# module.net
KiCad netlist of a schematic drawn in EAGLE
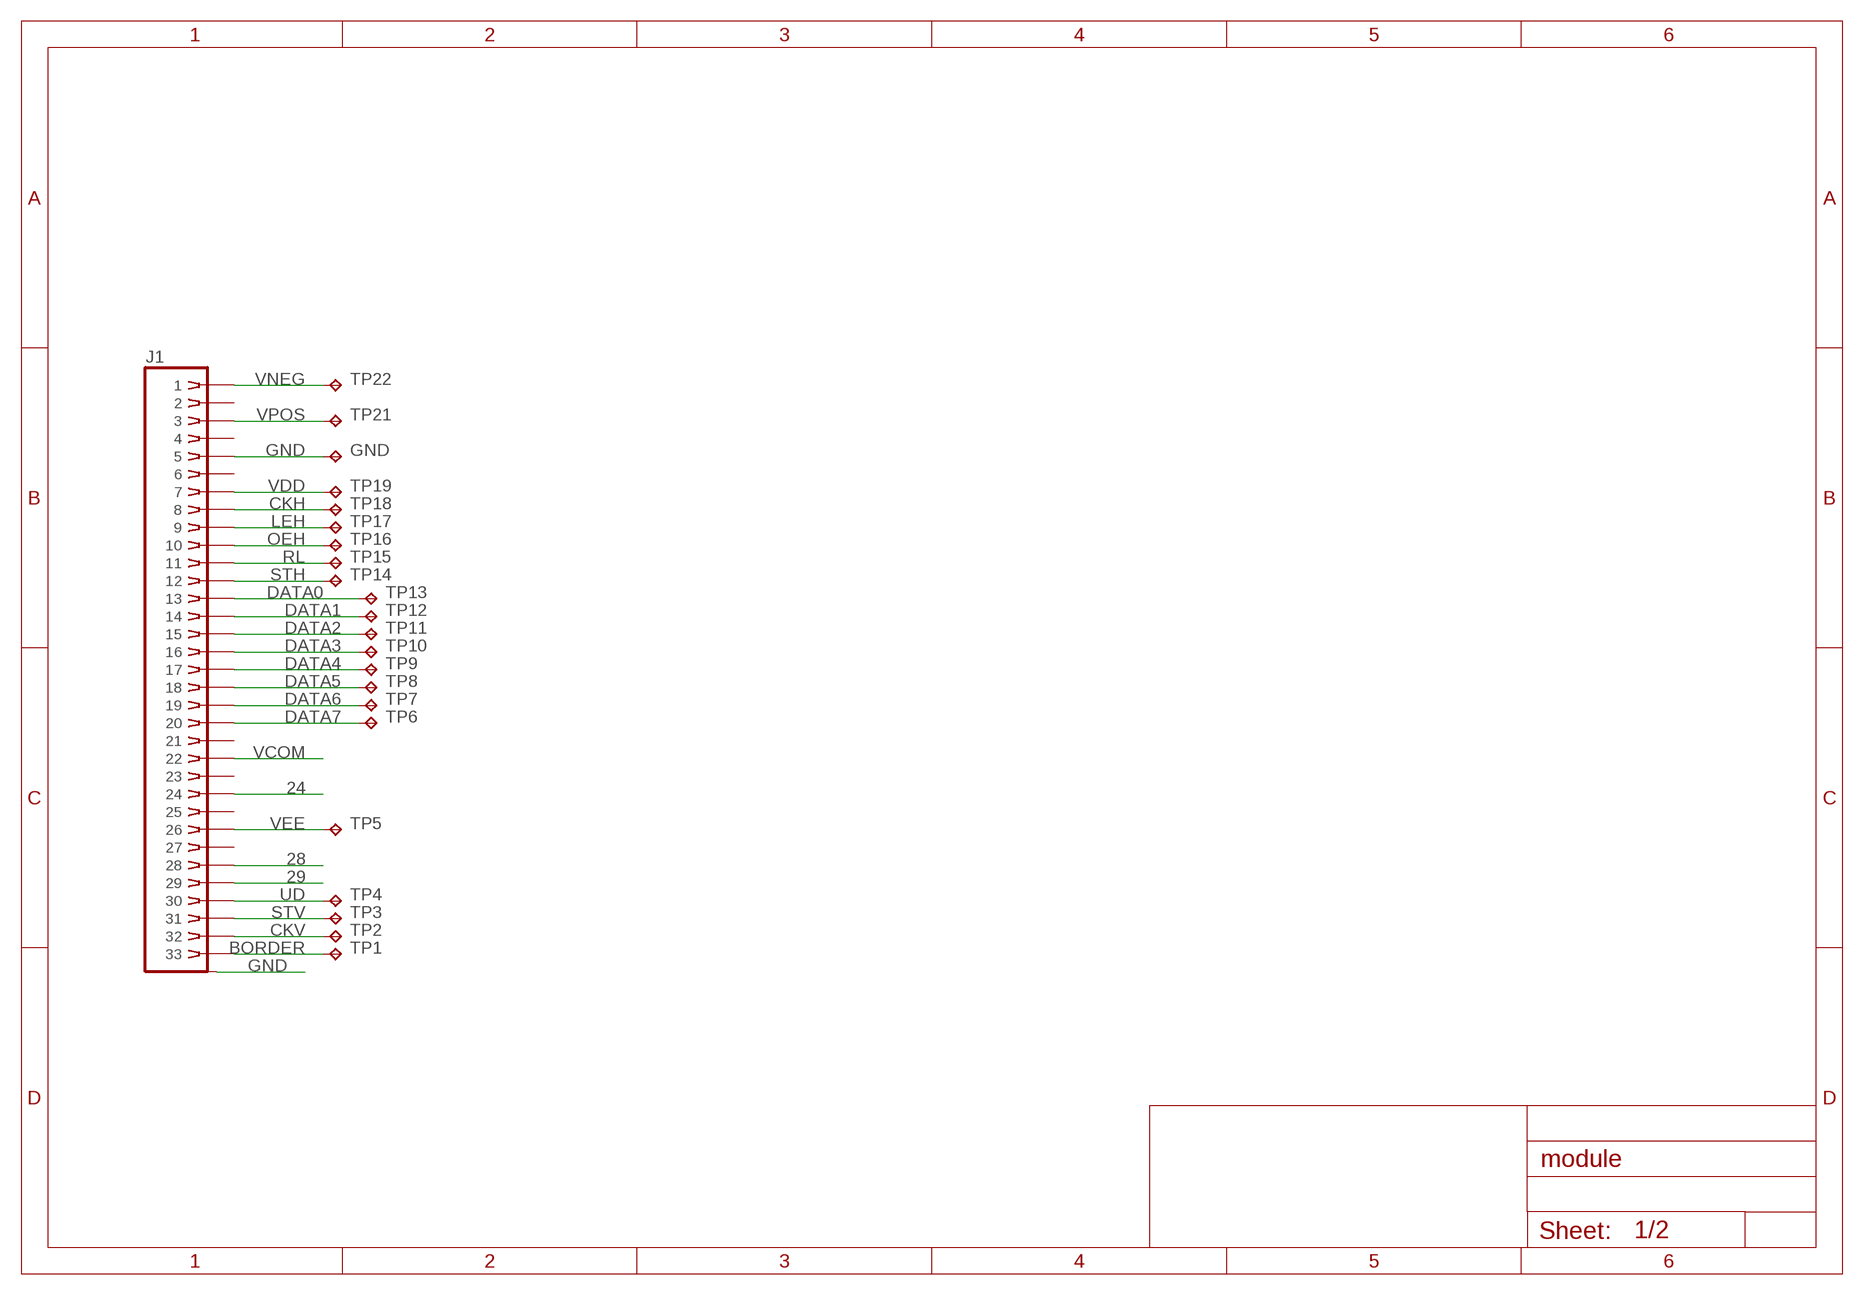
[diagram p0: schematic, sheet 1]
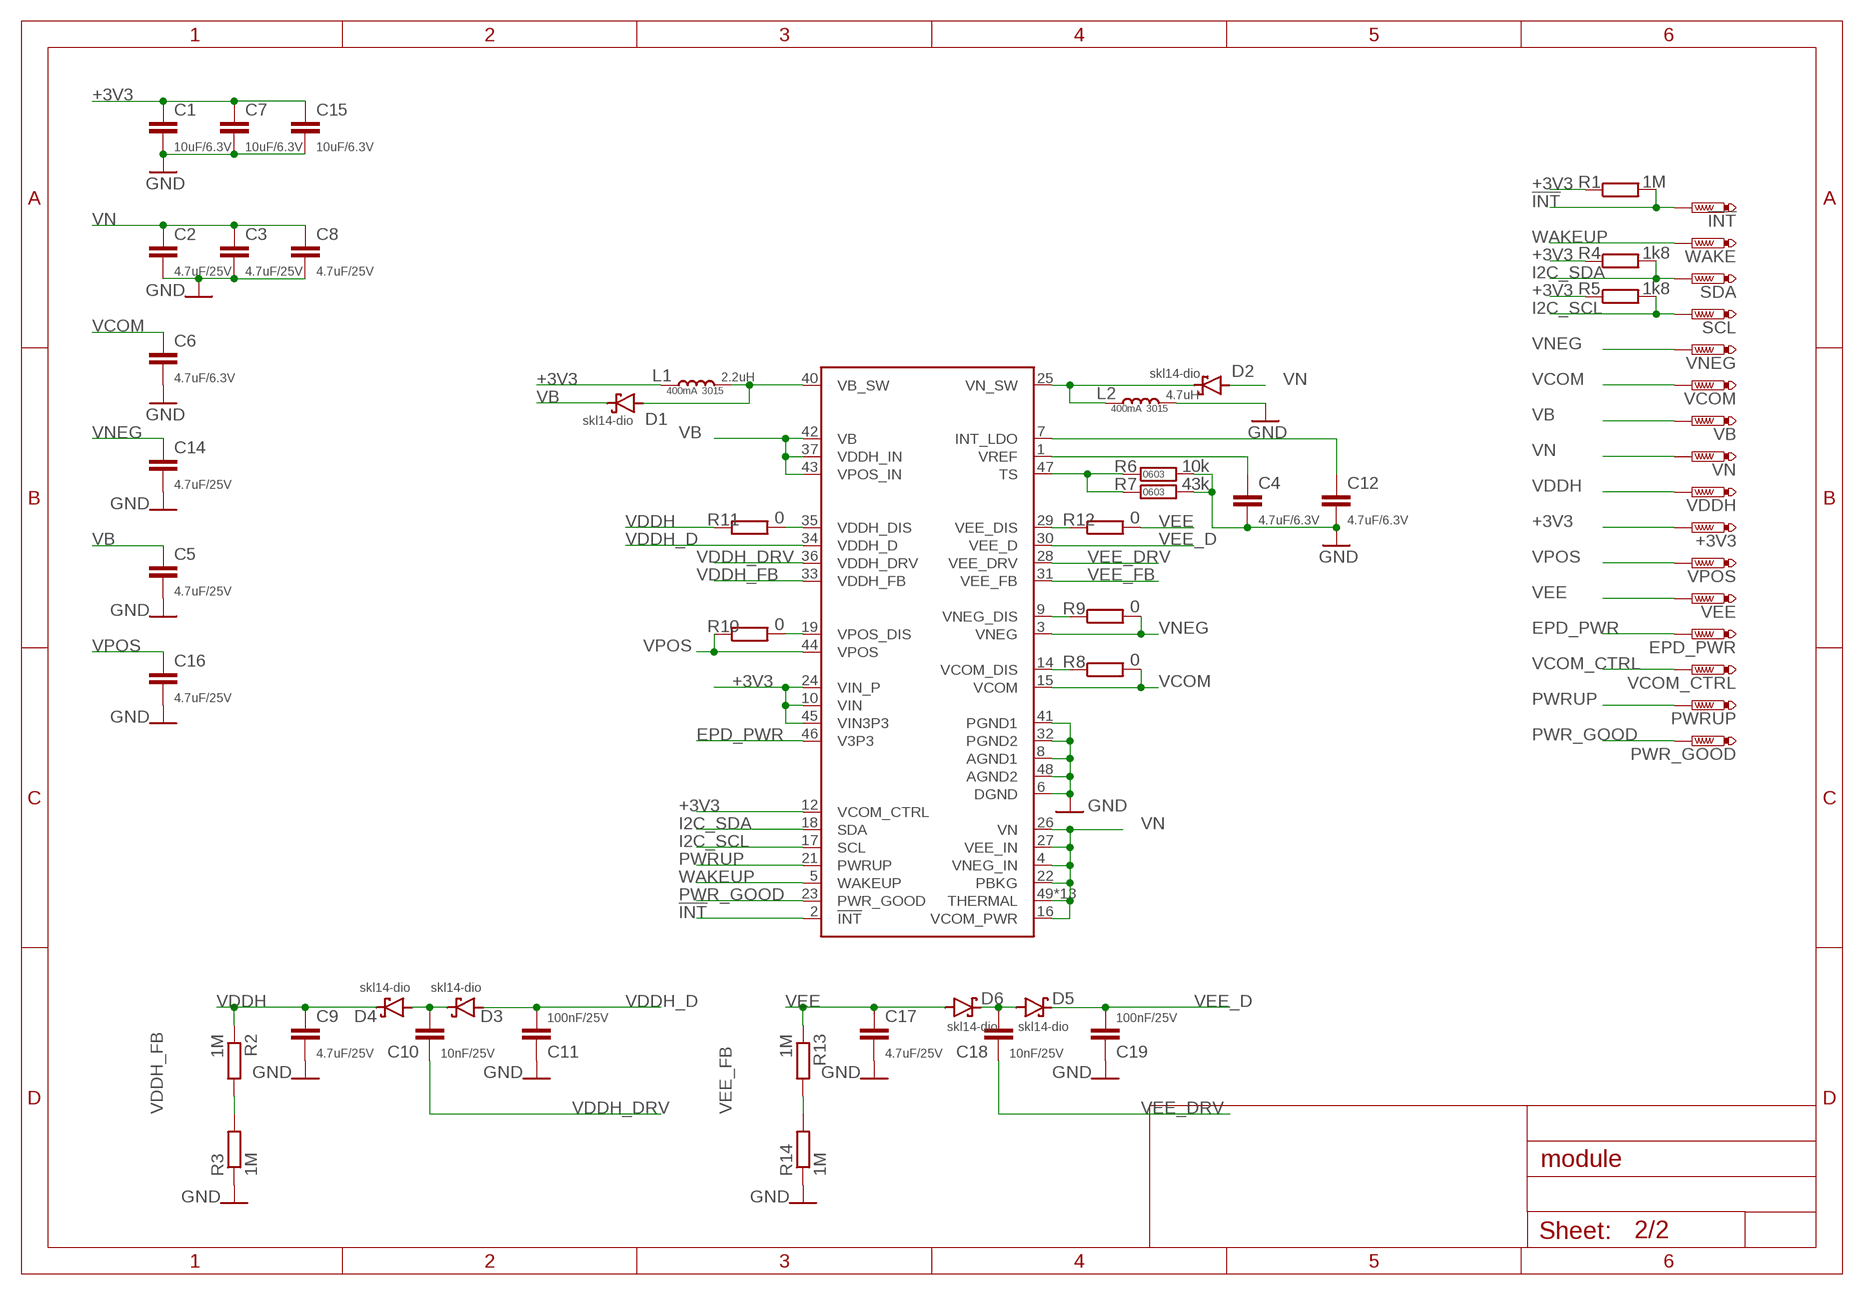
[diagram p1: schematic, sheet 2]

(export (version "E")
  (design (tool "Eeschema 10.0.6"))
  (components
    (comp (ref "!INT")
      (value "PTR1B1,27")
      (footprint "eagle-import:B1,27")
      (libsource (lib "eagle-import") (part "PTR1B1,27"))
    )
    (comp (ref "+3V3")
      (value "PTR1B1,27")
      (footprint "eagle-import:B1,27")
      (libsource (lib "eagle-import") (part "PTR1B1,27"))
    )
    (comp (ref "C1")
      (value "10uF/6.3V")
      (footprint "eagle-import:C0805")
      (libsource (lib "eagle-import") (part "C-EUC0805"))
    )
    (comp (ref "C2")
      (value "4.7uF/25V")
      (footprint "eagle-import:C0805")
      (libsource (lib "eagle-import") (part "C-EUC0805"))
    )
    (comp (ref "C3")
      (value "4.7uF/25V")
      (footprint "eagle-import:C0805")
      (libsource (lib "eagle-import") (part "C-EUC0805"))
    )
    (comp (ref "C4")
      (value "4.7uF/6.3V")
      (footprint "eagle-import:C0603")
      (libsource (lib "eagle-import") (part "C-EUC0603"))
    )
    (comp (ref "C5")
      (value "4.7uF/25V")
      (footprint "eagle-import:C0805")
      (libsource (lib "eagle-import") (part "C-EUC0805"))
    )
    (comp (ref "C6")
      (value "4.7uF/6.3V")
      (footprint "eagle-import:C0603")
      (libsource (lib "eagle-import") (part "C-EUC0603"))
    )
    (comp (ref "C7")
      (value "10uF/6.3V")
      (footprint "eagle-import:C0805")
      (libsource (lib "eagle-import") (part "C-EUC0805"))
    )
    (comp (ref "C8")
      (value "4.7uF/25V")
      (footprint "eagle-import:C0805")
      (libsource (lib "eagle-import") (part "C-EUC0805"))
    )
    (comp (ref "C9")
      (value "4.7uF/25V")
      (footprint "eagle-import:C0805")
      (libsource (lib "eagle-import") (part "C-EUC0805"))
    )
    (comp (ref "C10")
      (value "10nF/25V")
      (footprint "eagle-import:C0402")
      (libsource (lib "eagle-import") (part "C-EUC0402"))
    )
    (comp (ref "C11")
      (value "100nF/25V")
      (footprint "eagle-import:C0603")
      (libsource (lib "eagle-import") (part "C-EUC0603"))
    )
    (comp (ref "C12")
      (value "4.7uF/6.3V")
      (footprint "eagle-import:C0603")
      (libsource (lib "eagle-import") (part "C-EUC0603"))
    )
    (comp (ref "C14")
      (value "4.7uF/25V")
      (footprint "eagle-import:C0805")
      (libsource (lib "eagle-import") (part "C-EUC0805"))
    )
    (comp (ref "C15")
      (value "10uF/6.3V")
      (footprint "eagle-import:C0805")
      (libsource (lib "eagle-import") (part "C-EUC0805"))
    )
    (comp (ref "C16")
      (value "4.7uF/25V")
      (footprint "eagle-import:C0805")
      (libsource (lib "eagle-import") (part "C-EUC0805"))
    )
    (comp (ref "C17")
      (value "4.7uF/25V")
      (footprint "eagle-import:C0805")
      (libsource (lib "eagle-import") (part "C-EUC0805"))
    )
    (comp (ref "C18")
      (value "10nF/25V")
      (footprint "eagle-import:C0402")
      (libsource (lib "eagle-import") (part "C-EUC0402"))
    )
    (comp (ref "C19")
      (value "100nF/25V")
      (footprint "eagle-import:C0603")
      (libsource (lib "eagle-import") (part "C-EUC0603"))
    )
    (comp (ref "D1")
      (value "skl14-dio")
      (footprint "eagle-import:SODFL3718X130")
      (libsource (lib "eagle-import") (part "SKL14"))
    )
    (comp (ref "D2")
      (value "skl14-dio")
      (footprint "eagle-import:SODFL3718X130")
      (libsource (lib "eagle-import") (part "SKL14"))
    )
    (comp (ref "D3")
      (value "skl14-dio")
      (footprint "eagle-import:SODFL3718X130")
      (libsource (lib "eagle-import") (part "SKL14"))
    )
    (comp (ref "D4")
      (value "skl14-dio")
      (footprint "eagle-import:SODFL3718X130")
      (libsource (lib "eagle-import") (part "SKL14"))
    )
    (comp (ref "D5")
      (value "skl14-dio")
      (footprint "eagle-import:SODFL3718X130")
      (libsource (lib "eagle-import") (part "SKL14"))
    )
    (comp (ref "D6")
      (value "skl14-dio")
      (footprint "eagle-import:SODFL3718X130")
      (libsource (lib "eagle-import") (part "SKL14"))
    )
    (comp (ref "EPD_PWR")
      (value "PTR1B1,27")
      (footprint "eagle-import:B1,27")
      (libsource (lib "eagle-import") (part "PTR1B1,27"))
    )
    (comp (ref "L1")
      (value "2.2uH")
      (footprint "eagle-import:L3230M")
      (fields (field (name "PACKAGE") "3015") (field (name "CURRENT") "400mA"))
      (libsource (lib "eagle-import") (part "DJNR3015"))
    )
    (comp (ref "L2")
      (value "4.7uH")
      (footprint "eagle-import:L3230M")
      (fields (field (name "PACKAGE") "3015") (field (name "CURRENT") "400mA"))
      (libsource (lib "eagle-import") (part "DJNR3015"))
    )
    (comp (ref "PWRUP")
      (value "PTR1B1,27")
      (footprint "eagle-import:B1,27")
      (libsource (lib "eagle-import") (part "PTR1B1,27"))
    )
    (comp (ref "PWR_GOOD")
      (value "PTR1B1,27")
      (footprint "eagle-import:B1,27")
      (libsource (lib "eagle-import") (part "PTR1B1,27"))
    )
    (comp (ref "R1")
      (value "1M")
      (footprint "eagle-import:R0603")
      (libsource (lib "eagle-import") (part "R-EU_R0603"))
    )
    (comp (ref "R2")
      (value "1M")
      (footprint "eagle-import:R0603")
      (libsource (lib "eagle-import") (part "R-EU_R0603"))
    )
    (comp (ref "R3")
      (value "1M")
      (footprint "eagle-import:R0603")
      (libsource (lib "eagle-import") (part "R-EU_R0603"))
    )
    (comp (ref "R4")
      (value "1k8")
      (footprint "eagle-import:R0603")
      (libsource (lib "eagle-import") (part "R-EU_R0603"))
    )
    (comp (ref "R5")
      (value "1k8")
      (footprint "eagle-import:R0603")
      (libsource (lib "eagle-import") (part "R-EU_R0603"))
    )
    (comp (ref "R6")
      (value "10k")
      (footprint "eagle-import:R0603")
      (fields (field (name "PACKAGE") "0603"))
      (libsource (lib "eagle-import") (part "RES-0603"))
    )
    (comp (ref "R7")
      (value "43k")
      (footprint "eagle-import:R0603")
      (fields (field (name "PACKAGE") "0603"))
      (libsource (lib "eagle-import") (part "RES-0603"))
    )
    (comp (ref "R8")
      (value "0")
      (footprint "eagle-import:R0402")
      (libsource (lib "eagle-import") (part "R-EU_R0402"))
    )
    (comp (ref "R9")
      (value "0")
      (footprint "eagle-import:R0402")
      (libsource (lib "eagle-import") (part "R-EU_R0402"))
    )
    (comp (ref "R10")
      (value "0")
      (footprint "eagle-import:R0402")
      (libsource (lib "eagle-import") (part "R-EU_R0402"))
    )
    (comp (ref "R11")
      (value "0")
      (footprint "eagle-import:R0402")
      (libsource (lib "eagle-import") (part "R-EU_R0402"))
    )
    (comp (ref "R12")
      (value "0")
      (footprint "eagle-import:R0402")
      (libsource (lib "eagle-import") (part "R-EU_R0402"))
    )
    (comp (ref "R13")
      (value "1M")
      (footprint "eagle-import:R0603")
      (libsource (lib "eagle-import") (part "R-EU_R0603"))
    )
    (comp (ref "R14")
      (value "1M")
      (footprint "eagle-import:R0603")
      (libsource (lib "eagle-import") (part "R-EU_R0603"))
    )
    (comp (ref "SCL")
      (value "PTR1B1,27")
      (footprint "eagle-import:B1,27")
      (libsource (lib "eagle-import") (part "PTR1B1,27"))
    )
    (comp (ref "SDA")
      (value "PTR1B1,27")
      (footprint "eagle-import:B1,27")
      (libsource (lib "eagle-import") (part "PTR1B1,27"))
    )
    (comp (ref "U1")
      (value "TPS65185")
      (footprint "eagle-import:QFN50P700X700X100-49T410")
      (libsource (lib "eagle-import") (part "TPS65185"))
    )
    (comp (ref "VB")
      (value "PTR1B1,27")
      (footprint "eagle-import:B1,27")
      (libsource (lib "eagle-import") (part "PTR1B1,27"))
    )
    (comp (ref "VCOM")
      (value "PTR1B1,27")
      (footprint "eagle-import:B1,27")
      (libsource (lib "eagle-import") (part "PTR1B1,27"))
    )
    (comp (ref "VCOM_CTRL")
      (value "PTR1B1,27")
      (footprint "eagle-import:B1,27")
      (libsource (lib "eagle-import") (part "PTR1B1,27"))
    )
    (comp (ref "VDDH")
      (value "PTR1B1,27")
      (footprint "eagle-import:B1,27")
      (libsource (lib "eagle-import") (part "PTR1B1,27"))
    )
    (comp (ref "VEE")
      (value "PTR1B1,27")
      (footprint "eagle-import:B1,27")
      (libsource (lib "eagle-import") (part "PTR1B1,27"))
    )
    (comp (ref "VN")
      (value "PTR1B1,27")
      (footprint "eagle-import:B1,27")
      (libsource (lib "eagle-import") (part "PTR1B1,27"))
    )
    (comp (ref "VNEG")
      (value "PTR1B1,27")
      (footprint "eagle-import:B1,27")
      (libsource (lib "eagle-import") (part "PTR1B1,27"))
    )
    (comp (ref "VPOS")
      (value "PTR1B1,27")
      (footprint "eagle-import:B1,27")
      (libsource (lib "eagle-import") (part "PTR1B1,27"))
    )
    (comp (ref "WAKE")
      (value "PTR1B1,27")
      (footprint "eagle-import:B1,27")
      (libsource (lib "eagle-import") (part "PTR1B1,27"))
    )
    (comp (ref "GND")
      (value "TPB1,27")
      (footprint "eagle-import:B1,27")
      (libsource (lib "eagle-import") (part "TPB1,27"))
    )
    (comp (ref "J1")
      (value "SFV33R")
      (footprint "eagle-import:SFV33R-1STE1LF")
      (libsource (lib "eagle-import") (part "SFV33R"))
    )
    (comp (ref "TP1")
      (value "TPB1,27")
      (footprint "eagle-import:B1,27")
      (libsource (lib "eagle-import") (part "TPB1,27"))
    )
    (comp (ref "TP2")
      (value "TPB1,27")
      (footprint "eagle-import:B1,27")
      (libsource (lib "eagle-import") (part "TPB1,27"))
    )
    (comp (ref "TP3")
      (value "TPB1,27")
      (footprint "eagle-import:B1,27")
      (libsource (lib "eagle-import") (part "TPB1,27"))
    )
    (comp (ref "TP4")
      (value "TPB1,27")
      (footprint "eagle-import:B1,27")
      (libsource (lib "eagle-import") (part "TPB1,27"))
    )
    (comp (ref "TP5")
      (value "TPB1,27")
      (footprint "eagle-import:B1,27")
      (libsource (lib "eagle-import") (part "TPB1,27"))
    )
    (comp (ref "TP6")
      (value "TPB1,27")
      (footprint "eagle-import:B1,27")
      (libsource (lib "eagle-import") (part "TPB1,27"))
    )
    (comp (ref "TP7")
      (value "TPB1,27")
      (footprint "eagle-import:B1,27")
      (libsource (lib "eagle-import") (part "TPB1,27"))
    )
    (comp (ref "TP8")
      (value "TPB1,27")
      (footprint "eagle-import:B1,27")
      (libsource (lib "eagle-import") (part "TPB1,27"))
    )
    (comp (ref "TP9")
      (value "TPB1,27")
      (footprint "eagle-import:B1,27")
      (libsource (lib "eagle-import") (part "TPB1,27"))
    )
    (comp (ref "TP10")
      (value "TPB1,27")
      (footprint "eagle-import:B1,27")
      (libsource (lib "eagle-import") (part "TPB1,27"))
    )
    (comp (ref "TP11")
      (value "TPB1,27")
      (footprint "eagle-import:B1,27")
      (libsource (lib "eagle-import") (part "TPB1,27"))
    )
    (comp (ref "TP12")
      (value "TPB1,27")
      (footprint "eagle-import:B1,27")
      (libsource (lib "eagle-import") (part "TPB1,27"))
    )
    (comp (ref "TP13")
      (value "TPB1,27")
      (footprint "eagle-import:B1,27")
      (libsource (lib "eagle-import") (part "TPB1,27"))
    )
    (comp (ref "TP14")
      (value "TPB1,27")
      (footprint "eagle-import:B1,27")
      (libsource (lib "eagle-import") (part "TPB1,27"))
    )
    (comp (ref "TP15")
      (value "TPB1,27")
      (footprint "eagle-import:B1,27")
      (libsource (lib "eagle-import") (part "TPB1,27"))
    )
    (comp (ref "TP16")
      (value "TPB1,27")
      (footprint "eagle-import:B1,27")
      (libsource (lib "eagle-import") (part "TPB1,27"))
    )
    (comp (ref "TP17")
      (value "TPB1,27")
      (footprint "eagle-import:B1,27")
      (libsource (lib "eagle-import") (part "TPB1,27"))
    )
    (comp (ref "TP18")
      (value "TPB1,27")
      (footprint "eagle-import:B1,27")
      (libsource (lib "eagle-import") (part "TPB1,27"))
    )
    (comp (ref "TP19")
      (value "TPB1,27")
      (footprint "eagle-import:B1,27")
      (libsource (lib "eagle-import") (part "TPB1,27"))
    )
    (comp (ref "TP21")
      (value "TPB1,27")
      (footprint "eagle-import:B1,27")
      (libsource (lib "eagle-import") (part "TPB1,27"))
    )
    (comp (ref "TP22")
      (value "TPB1,27")
      (footprint "eagle-import:B1,27")
      (libsource (lib "eagle-import") (part "TPB1,27"))
    )
  )
  (nets
    (net (code "1") (name "+3V3") (class "Default")
      (node (ref "+3V3") (pin "TP") (pinfunction "TP_TP") (pintype "input"))
      (node (ref "C1") (pin "1") (pinfunction "1_1") (pintype "passive"))
      (node (ref "C15") (pin "1") (pinfunction "1_1") (pintype "passive"))
      (node (ref "C7") (pin "1") (pinfunction "1_1") (pintype "passive"))
      (node (ref "L1") (pin "1") (pinfunction "1_1") (pintype "passive"))
      (node (ref "R1") (pin "1") (pinfunction "1_1") (pintype "passive"))
      (node (ref "R4") (pin "1") (pinfunction "1_1") (pintype "passive"))
      (node (ref "R5") (pin "1") (pinfunction "1_1") (pintype "passive"))
      (node (ref "U1") (pin "10") (pinfunction "VIN_10") (pintype "bidirectional"))
      (node (ref "U1") (pin "12") (pinfunction "VCOM_CTRL_12") (pintype "bidirectional"))
      (node (ref "U1") (pin "24") (pinfunction "VIN_P_24") (pintype "bidirectional"))
      (node (ref "U1") (pin "45") (pinfunction "VIN3P3_45") (pintype "bidirectional"))
    )
    (net (code "2") (name "24") (class "Default")
      (node (ref "J1") (pin "24") (pinfunction "24_24") (pintype "passive"))
    )
    (net (code "3") (name "28") (class "Default")
      (node (ref "J1") (pin "28") (pinfunction "28_28") (pintype "passive"))
    )
    (net (code "4") (name "29") (class "Default")
      (node (ref "J1") (pin "29") (pinfunction "29_29") (pintype "passive"))
    )
    (net (code "5") (name "BORDER") (class "Default")
      (node (ref "J1") (pin "33") (pinfunction "33_33") (pintype "passive"))
      (node (ref "TP1") (pin "TP") (pinfunction "TP_TP") (pintype "input"))
    )
    (net (code "6") (name "CKH") (class "Default")
      (node (ref "J1") (pin "8") (pinfunction "8_8") (pintype "passive"))
      (node (ref "TP18") (pin "TP") (pinfunction "TP_TP") (pintype "input"))
    )
    (net (code "7") (name "CKV") (class "Default")
      (node (ref "J1") (pin "32") (pinfunction "32_32") (pintype "passive"))
      (node (ref "TP2") (pin "TP") (pinfunction "TP_TP") (pintype "input"))
    )
    (net (code "8") (name "DATA0") (class "Default")
      (node (ref "J1") (pin "13") (pinfunction "13_13") (pintype "passive"))
      (node (ref "TP13") (pin "TP") (pinfunction "TP_TP") (pintype "input"))
    )
    (net (code "9") (name "DATA1") (class "Default")
      (node (ref "J1") (pin "14") (pinfunction "14_14") (pintype "passive"))
      (node (ref "TP12") (pin "TP") (pinfunction "TP_TP") (pintype "input"))
    )
    (net (code "10") (name "DATA2") (class "Default")
      (node (ref "J1") (pin "15") (pinfunction "15_15") (pintype "passive"))
      (node (ref "TP11") (pin "TP") (pinfunction "TP_TP") (pintype "input"))
    )
    (net (code "11") (name "DATA3") (class "Default")
      (node (ref "J1") (pin "16") (pinfunction "16_16") (pintype "passive"))
      (node (ref "TP10") (pin "TP") (pinfunction "TP_TP") (pintype "input"))
    )
    (net (code "12") (name "DATA4") (class "Default")
      (node (ref "J1") (pin "17") (pinfunction "17_17") (pintype "passive"))
      (node (ref "TP9") (pin "TP") (pinfunction "TP_TP") (pintype "input"))
    )
    (net (code "13") (name "DATA5") (class "Default")
      (node (ref "J1") (pin "18") (pinfunction "18_18") (pintype "passive"))
      (node (ref "TP8") (pin "TP") (pinfunction "TP_TP") (pintype "input"))
    )
    (net (code "14") (name "DATA6") (class "Default")
      (node (ref "J1") (pin "19") (pinfunction "19_19") (pintype "passive"))
      (node (ref "TP7") (pin "TP") (pinfunction "TP_TP") (pintype "input"))
    )
    (net (code "15") (name "DATA7") (class "Default")
      (node (ref "J1") (pin "20") (pinfunction "20_20") (pintype "passive"))
      (node (ref "TP6") (pin "TP") (pinfunction "TP_TP") (pintype "input"))
    )
    (net (code "16") (name "EPD_PWR") (class "Default")
      (node (ref "EPD_PWR") (pin "TP") (pinfunction "TP_TP") (pintype "input"))
      (node (ref "U1") (pin "46") (pinfunction "V3P3_46") (pintype "bidirectional"))
    )
    (net (code "17") (name "GND") (class "Default")
      (node (ref "C1") (pin "2") (pinfunction "2_2") (pintype "passive"))
      (node (ref "C11") (pin "2") (pinfunction "2_2") (pintype "passive"))
      (node (ref "C12") (pin "2") (pinfunction "2_2") (pintype "passive"))
      (node (ref "C14") (pin "2") (pinfunction "2_2") (pintype "passive"))
      (node (ref "C15") (pin "2") (pinfunction "2_2") (pintype "passive"))
      (node (ref "C16") (pin "2") (pinfunction "2_2") (pintype "passive"))
      (node (ref "C17") (pin "2") (pinfunction "2_2") (pintype "passive"))
      (node (ref "C19") (pin "2") (pinfunction "2_2") (pintype "passive"))
      (node (ref "C2") (pin "2") (pinfunction "2_2") (pintype "passive"))
      (node (ref "C3") (pin "2") (pinfunction "2_2") (pintype "passive"))
      (node (ref "C4") (pin "2") (pinfunction "2_2") (pintype "passive"))
      (node (ref "C5") (pin "2") (pinfunction "2_2") (pintype "passive"))
      (node (ref "C6") (pin "2") (pinfunction "2_2") (pintype "passive"))
      (node (ref "C7") (pin "2") (pinfunction "2_2") (pintype "passive"))
      (node (ref "C8") (pin "2") (pinfunction "2_2") (pintype "passive"))
      (node (ref "C9") (pin "2") (pinfunction "2_2") (pintype "passive"))
      (node (ref "GND") (pin "TP") (pinfunction "TP_TP") (pintype "input"))
      (node (ref "J1") (pin "5") (pinfunction "5_5") (pintype "passive"))
      (node (ref "J1") (pin "SHLD1") (pinfunction "SHLD_SHLD1") (pintype "power_in"))
      (node (ref "J1") (pin "SHLD2") (pinfunction "SHLD_SHLD2") (pintype "power_in"))
      (node (ref "L2") (pin "2") (pinfunction "2_2") (pintype "passive"))
      (node (ref "R14") (pin "1") (pinfunction "1_1") (pintype "passive"))
      (node (ref "R3") (pin "1") (pinfunction "1_1") (pintype "passive"))
      (node (ref "R6") (pin "2") (pinfunction "2_2") (pintype "passive"))
      (node (ref "R7") (pin "2") (pinfunction "2_2") (pintype "passive"))
      (node (ref "U1") (pin "32") (pinfunction "PGND2_32") (pintype "bidirectional"))
      (node (ref "U1") (pin "41") (pinfunction "PGND1_41") (pintype "bidirectional"))
      (node (ref "U1") (pin "48") (pinfunction "AGND2_48") (pintype "bidirectional"))
      (node (ref "U1") (pin "6") (pinfunction "DGND_6") (pintype "bidirectional"))
      (node (ref "U1") (pin "8") (pinfunction "AGND1_8") (pintype "bidirectional"))
    )
    (net (code "18") (name "I2C_SCL") (class "Default")
      (node (ref "R5") (pin "2") (pinfunction "2_2") (pintype "passive"))
      (node (ref "SCL") (pin "TP") (pinfunction "TP_TP") (pintype "input"))
      (node (ref "U1") (pin "17") (pinfunction "SCL_17") (pintype "bidirectional"))
    )
    (net (code "19") (name "I2C_SDA") (class "Default")
      (node (ref "R4") (pin "2") (pinfunction "2_2") (pintype "passive"))
      (node (ref "SDA") (pin "TP") (pinfunction "TP_TP") (pintype "input"))
      (node (ref "U1") (pin "18") (pinfunction "SDA_18") (pintype "bidirectional"))
    )
    (net (code "20") (name "LEH") (class "Default")
      (node (ref "J1") (pin "9") (pinfunction "9_9") (pintype "passive"))
      (node (ref "TP17") (pin "TP") (pinfunction "TP_TP") (pintype "input"))
    )
    (net (code "21") (name "Net-(C10-Pad1)") (class "Default")
      (node (ref "C10") (pin "1") (pinfunction "1_1") (pintype "passive"))
      (node (ref "D3") (pin "C") (pinfunction "C_C") (pintype "passive"))
      (node (ref "D4") (pin "A") (pinfunction "A_A") (pintype "passive"))
    )
    (net (code "22") (name "Net-(C18-Pad1)") (class "Default")
      (node (ref "C18") (pin "1") (pinfunction "1_1") (pintype "passive"))
      (node (ref "D5") (pin "A") (pinfunction "A_A") (pintype "passive"))
      (node (ref "D6") (pin "C") (pinfunction "C_C") (pintype "passive"))
    )
    (net (code "23") (name "Net-(U1-INT_LDO)") (class "Default")
      (node (ref "C12") (pin "1") (pinfunction "1_1") (pintype "passive"))
      (node (ref "U1") (pin "7") (pinfunction "INT_LDO_7") (pintype "bidirectional"))
    )
    (net (code "24") (name "Net-(U1-TS)") (class "Default")
      (node (ref "R6") (pin "1") (pinfunction "1_1") (pintype "passive"))
      (node (ref "R7") (pin "1") (pinfunction "1_1") (pintype "passive"))
      (node (ref "U1") (pin "47") (pinfunction "TS_47") (pintype "bidirectional"))
    )
    (net (code "25") (name "Net-(U1-VB_SW)") (class "Default")
      (node (ref "D1") (pin "A") (pinfunction "A_A") (pintype "passive"))
      (node (ref "L1") (pin "2") (pinfunction "2_2") (pintype "passive"))
      (node (ref "U1") (pin "40") (pinfunction "VB_SW_40") (pintype "bidirectional"))
    )
    (net (code "26") (name "Net-(U1-VCOM_DIS)") (class "Default")
      (node (ref "R8") (pin "1") (pinfunction "1_1") (pintype "passive"))
      (node (ref "U1") (pin "14") (pinfunction "VCOM_DIS_14") (pintype "bidirectional"))
    )
    (net (code "27") (name "Net-(U1-VDDH_DIS)") (class "Default")
      (node (ref "R11") (pin "2") (pinfunction "2_2") (pintype "passive"))
      (node (ref "U1") (pin "35") (pinfunction "VDDH_DIS_35") (pintype "bidirectional"))
    )
    (net (code "28") (name "Net-(U1-VEE_DIS)") (class "Default")
      (node (ref "R12") (pin "1") (pinfunction "1_1") (pintype "passive"))
      (node (ref "U1") (pin "29") (pinfunction "VEE_DIS_29") (pintype "bidirectional"))
    )
    (net (code "29") (name "Net-(U1-VNEG_DIS)") (class "Default")
      (node (ref "R9") (pin "1") (pinfunction "1_1") (pintype "passive"))
      (node (ref "U1") (pin "9") (pinfunction "VNEG_DIS_9") (pintype "bidirectional"))
    )
    (net (code "30") (name "Net-(U1-VN_SW)") (class "Default")
      (node (ref "D2") (pin "C") (pinfunction "C_C") (pintype "passive"))
      (node (ref "L2") (pin "1") (pinfunction "1_1") (pintype "passive"))
      (node (ref "U1") (pin "25") (pinfunction "VN_SW_25") (pintype "bidirectional"))
    )
    (net (code "31") (name "Net-(U1-VPOS_DIS)") (class "Default")
      (node (ref "R10") (pin "2") (pinfunction "2_2") (pintype "passive"))
      (node (ref "U1") (pin "19") (pinfunction "VPOS_DIS_19") (pintype "bidirectional"))
    )
    (net (code "32") (name "Net-(U1-VREF)") (class "Default")
      (node (ref "C4") (pin "1") (pinfunction "1_1") (pintype "passive"))
      (node (ref "U1") (pin "1") (pinfunction "VREF_1") (pintype "bidirectional"))
    )
    (net (code "33") (name "OEH") (class "Default")
      (node (ref "J1") (pin "10") (pinfunction "10_10") (pintype "passive"))
      (node (ref "TP16") (pin "TP") (pinfunction "TP_TP") (pintype "input"))
    )
    (net (code "34") (name "PWRUP") (class "Default")
      (node (ref "PWRUP") (pin "TP") (pinfunction "TP_TP") (pintype "input"))
      (node (ref "U1") (pin "21") (pinfunction "PWRUP_21") (pintype "bidirectional"))
    )
    (net (code "35") (name "PWR_GOOD") (class "Default")
      (node (ref "PWR_GOOD") (pin "TP") (pinfunction "TP_TP") (pintype "input"))
      (node (ref "U1") (pin "23") (pinfunction "PWR_GOOD_23") (pintype "bidirectional"))
    )
    (net (code "36") (name "RL") (class "Default")
      (node (ref "J1") (pin "11") (pinfunction "11_11") (pintype "passive"))
      (node (ref "TP15") (pin "TP") (pinfunction "TP_TP") (pintype "input"))
    )
    (net (code "37") (name "STH") (class "Default")
      (node (ref "J1") (pin "12") (pinfunction "12_12") (pintype "passive"))
      (node (ref "TP14") (pin "TP") (pinfunction "TP_TP") (pintype "input"))
    )
    (net (code "38") (name "STV") (class "Default")
      (node (ref "J1") (pin "31") (pinfunction "31_31") (pintype "passive"))
      (node (ref "TP3") (pin "TP") (pinfunction "TP_TP") (pintype "input"))
    )
    (net (code "39") (name "UD") (class "Default")
      (node (ref "J1") (pin "30") (pinfunction "30_30") (pintype "passive"))
      (node (ref "TP4") (pin "TP") (pinfunction "TP_TP") (pintype "input"))
    )
    (net (code "40") (name "VB") (class "Default")
      (node (ref "C5") (pin "1") (pinfunction "1_1") (pintype "passive"))
      (node (ref "D1") (pin "C") (pinfunction "C_C") (pintype "passive"))
      (node (ref "U1") (pin "37") (pinfunction "VDDH_IN_37") (pintype "bidirectional"))
      (node (ref "U1") (pin "42") (pinfunction "VB_42") (pintype "bidirectional"))
      (node (ref "U1") (pin "43") (pinfunction "VPOS_IN_43") (pintype "bidirectional"))
      (node (ref "VB") (pin "TP") (pinfunction "TP_TP") (pintype "input"))
    )
    (net (code "41") (name "VCOM") (class "Default")
      (node (ref "C6") (pin "1") (pinfunction "1_1") (pintype "passive"))
      (node (ref "J1") (pin "22") (pinfunction "22_22") (pintype "passive"))
      (node (ref "R8") (pin "2") (pinfunction "2_2") (pintype "passive"))
      (node (ref "U1") (pin "15") (pinfunction "VCOM_15") (pintype "bidirectional"))
      (node (ref "VCOM") (pin "TP") (pinfunction "TP_TP") (pintype "input"))
    )
    (net (code "42") (name "VCOM_CTRL") (class "Default")
      (node (ref "VCOM_CTRL") (pin "TP") (pinfunction "TP_TP") (pintype "input"))
    )
    (net (code "43") (name "VDD") (class "Default")
      (node (ref "J1") (pin "7") (pinfunction "7_7") (pintype "passive"))
      (node (ref "TP19") (pin "TP") (pinfunction "TP_TP") (pintype "input"))
    )
    (net (code "44") (name "VDDH") (class "Default")
      (node (ref "C9") (pin "1") (pinfunction "1_1") (pintype "passive"))
      (node (ref "D4") (pin "C") (pinfunction "C_C") (pintype "passive"))
      (node (ref "R11") (pin "1") (pinfunction "1_1") (pintype "passive"))
      (node (ref "R2") (pin "1") (pinfunction "1_1") (pintype "passive"))
      (node (ref "VDDH") (pin "TP") (pinfunction "TP_TP") (pintype "input"))
    )
    (net (code "45") (name "VDDH_D") (class "Default")
      (node (ref "C11") (pin "1") (pinfunction "1_1") (pintype "passive"))
      (node (ref "D3") (pin "A") (pinfunction "A_A") (pintype "passive"))
      (node (ref "U1") (pin "34") (pinfunction "VDDH_D_34") (pintype "bidirectional"))
    )
    (net (code "46") (name "VDDH_DRV") (class "Default")
      (node (ref "C10") (pin "2") (pinfunction "2_2") (pintype "passive"))
      (node (ref "U1") (pin "36") (pinfunction "VDDH_DRV_36") (pintype "bidirectional"))
    )
    (net (code "47") (name "VDDH_FB") (class "Default")
      (node (ref "R2") (pin "2") (pinfunction "2_2") (pintype "passive"))
      (node (ref "R3") (pin "2") (pinfunction "2_2") (pintype "passive"))
      (node (ref "U1") (pin "33") (pinfunction "VDDH_FB_33") (pintype "bidirectional"))
    )
    (net (code "48") (name "VEE") (class "Default")
      (node (ref "C17") (pin "1") (pinfunction "1_1") (pintype "passive"))
      (node (ref "D6") (pin "A") (pinfunction "A_A") (pintype "passive"))
      (node (ref "J1") (pin "26") (pinfunction "26_26") (pintype "passive"))
      (node (ref "R12") (pin "2") (pinfunction "2_2") (pintype "passive"))
      (node (ref "R13") (pin "1") (pinfunction "1_1") (pintype "passive"))
      (node (ref "TP5") (pin "TP") (pinfunction "TP_TP") (pintype "input"))
      (node (ref "VEE") (pin "TP") (pinfunction "TP_TP") (pintype "input"))
    )
    (net (code "49") (name "VEE_D") (class "Default")
      (node (ref "C19") (pin "1") (pinfunction "1_1") (pintype "passive"))
      (node (ref "D5") (pin "C") (pinfunction "C_C") (pintype "passive"))
      (node (ref "U1") (pin "30") (pinfunction "VEE_D_30") (pintype "bidirectional"))
    )
    (net (code "50") (name "VEE_DRV") (class "Default")
      (node (ref "C18") (pin "2") (pinfunction "2_2") (pintype "passive"))
      (node (ref "U1") (pin "28") (pinfunction "VEE_DRV_28") (pintype "bidirectional"))
    )
    (net (code "51") (name "VEE_FB") (class "Default")
      (node (ref "R13") (pin "2") (pinfunction "2_2") (pintype "passive"))
      (node (ref "R14") (pin "2") (pinfunction "2_2") (pintype "passive"))
      (node (ref "U1") (pin "31") (pinfunction "VEE_FB_31") (pintype "bidirectional"))
    )
    (net (code "52") (name "VN") (class "Default")
      (node (ref "C2") (pin "1") (pinfunction "1_1") (pintype "passive"))
      (node (ref "C3") (pin "1") (pinfunction "1_1") (pintype "passive"))
      (node (ref "C8") (pin "1") (pinfunction "1_1") (pintype "passive"))
      (node (ref "D2") (pin "A") (pinfunction "A_A") (pintype "passive"))
      (node (ref "U1") (pin "16") (pinfunction "VCOM_PWR_16") (pintype "bidirectional"))
      (node (ref "U1") (pin "22") (pinfunction "PBKG_22") (pintype "bidirectional"))
      (node (ref "U1") (pin "26") (pinfunction "VN_26") (pintype "bidirectional"))
      (node (ref "U1") (pin "27") (pinfunction "VEE_IN_27") (pintype "bidirectional"))
      (node (ref "U1") (pin "4") (pinfunction "VNEG_IN_4") (pintype "bidirectional"))
      (node (ref "U1") (pin "49") (pinfunction "THERMAL_49") (pintype "bidirectional"))
      (node (ref "U1") (pin "P$1") (pinfunction "THERMAL_P$1") (pintype "bidirectional"))
      (node (ref "U1") (pin "P$10") (pinfunction "THERMAL_P$10") (pintype "bidirectional"))
      (node (ref "U1") (pin "P$11") (pinfunction "THERMAL_P$11") (pintype "bidirectional"))
      (node (ref "U1") (pin "P$12") (pinfunction "THERMAL_P$12") (pintype "bidirectional"))
      (node (ref "U1") (pin "P$2") (pinfunction "THERMAL_P$2") (pintype "bidirectional"))
      (node (ref "U1") (pin "P$3") (pinfunction "THERMAL_P$3") (pintype "bidirectional"))
      (node (ref "U1") (pin "P$4") (pinfunction "THERMAL_P$4") (pintype "bidirectional"))
      (node (ref "U1") (pin "P$5") (pinfunction "THERMAL_P$5") (pintype "bidirectional"))
      (node (ref "U1") (pin "P$6") (pinfunction "THERMAL_P$6") (pintype "bidirectional"))
      (node (ref "U1") (pin "P$7") (pinfunction "THERMAL_P$7") (pintype "bidirectional"))
      (node (ref "U1") (pin "P$8") (pinfunction "THERMAL_P$8") (pintype "bidirectional"))
      (node (ref "U1") (pin "P$9") (pinfunction "THERMAL_P$9") (pintype "bidirectional"))
      (node (ref "VN") (pin "TP") (pinfunction "TP_TP") (pintype "input"))
    )
    (net (code "53") (name "VNEG") (class "Default")
      (node (ref "C14") (pin "1") (pinfunction "1_1") (pintype "passive"))
      (node (ref "J1") (pin "1") (pinfunction "1_1") (pintype "passive"))
      (node (ref "R9") (pin "2") (pinfunction "2_2") (pintype "passive"))
      (node (ref "TP22") (pin "TP") (pinfunction "TP_TP") (pintype "input"))
      (node (ref "U1") (pin "3") (pinfunction "VNEG_3") (pintype "bidirectional"))
      (node (ref "VNEG") (pin "TP") (pinfunction "TP_TP") (pintype "input"))
    )
    (net (code "54") (name "VPOS") (class "Default")
      (node (ref "C16") (pin "1") (pinfunction "1_1") (pintype "passive"))
      (node (ref "J1") (pin "3") (pinfunction "3_3") (pintype "passive"))
      (node (ref "R10") (pin "1") (pinfunction "1_1") (pintype "passive"))
      (node (ref "TP21") (pin "TP") (pinfunction "TP_TP") (pintype "input"))
      (node (ref "U1") (pin "44") (pinfunction "VPOS_44") (pintype "bidirectional"))
      (node (ref "VPOS") (pin "TP") (pinfunction "TP_TP") (pintype "input"))
    )
    (net (code "55") (name "WAKEUP") (class "Default")
      (node (ref "U1") (pin "5") (pinfunction "WAKEUP_5") (pintype "bidirectional"))
      (node (ref "WAKE") (pin "TP") (pinfunction "TP_TP") (pintype "input"))
    )
    (net (code "56") (name "unconnected-(J1-Pad2)") (class "Default")
      (node (ref "J1") (pin "2") (pinfunction "2_2") (pintype "passive"))
    )
    (net (code "57") (name "unconnected-(J1-Pad4)") (class "Default")
      (node (ref "J1") (pin "4") (pinfunction "4_4") (pintype "passive"))
    )
    (net (code "58") (name "unconnected-(J1-Pad6)") (class "Default")
      (node (ref "J1") (pin "6") (pinfunction "6_6") (pintype "passive"))
    )
    (net (code "59") (name "unconnected-(J1-Pad21)") (class "Default")
      (node (ref "J1") (pin "21") (pinfunction "21_21") (pintype "passive"))
    )
    (net (code "60") (name "unconnected-(J1-Pad23)") (class "Default")
      (node (ref "J1") (pin "23") (pinfunction "23_23") (pintype "passive"))
    )
    (net (code "61") (name "unconnected-(J1-Pad25)") (class "Default")
      (node (ref "J1") (pin "25") (pinfunction "25_25") (pintype "passive"))
    )
    (net (code "62") (name "unconnected-(J1-Pad27)") (class "Default")
      (node (ref "J1") (pin "27") (pinfunction "27_27") (pintype "passive"))
    )
    (net (code "63") (name "~{INT}") (class "Default")
      (node (ref "!INT") (pin "TP") (pinfunction "TP_TP") (pintype "input"))
      (node (ref "R1") (pin "2") (pinfunction "2_2") (pintype "passive"))
      (node (ref "U1") (pin "2") (pinfunction "~{INT}_2") (pintype "bidirectional"))
    )
  )
)
